# StreamDeck_CPU1-V0.net
KiCad netlist of a schematic drawn in Altium Designer
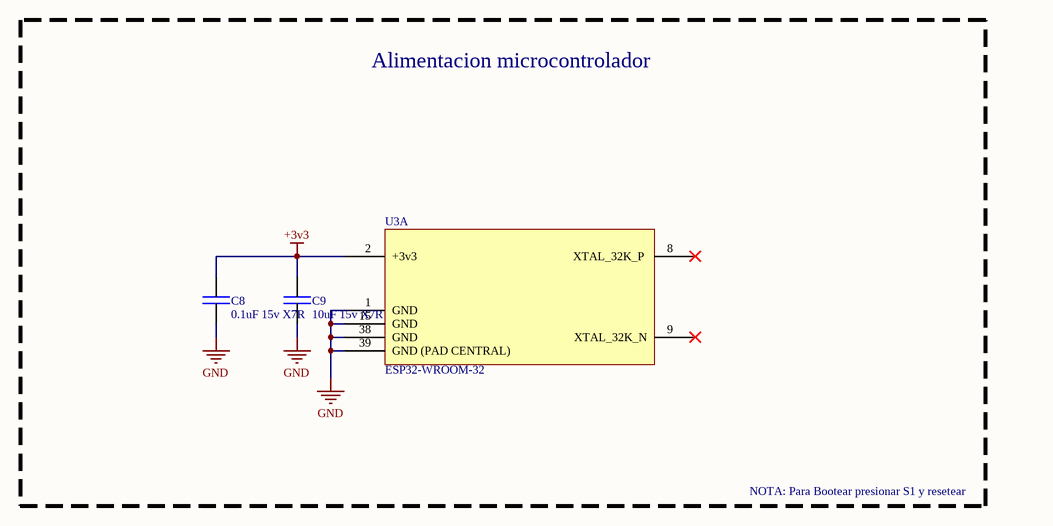
[diagram p0: StreamDeck_CPU1-V0.SchDoc]

(export (version "E")
  (design (tool "Eeschema 10.0.6"))
  (components
    (comp (ref "C8")
      (value "0.1uF 15v X7R")
      (footprint "C_0805")
      (description "Capacitor no polarizado")
      (libsource (lib "StreamDeck-V0") (part "Capacitor NP"))
    )
    (comp (ref "C9")
      (value "10uF 15v X7R")
      (footprint "C_0805")
      (description "Capacitor no polarizado")
      (libsource (lib "StreamDeck-V0") (part "Capacitor NP"))
    )
    (comp (ref "U3")
      (value "ESP32-WROOM-32")
      (footprint "Espressif ESP32-WROOM-32")
      (libsource (lib "StreamDeck-V0") (part "ESP32"))
    )
  )
  (nets
    (net (code "1") (name "+3v3") (class "Default")
      (node (ref "C8") (pin "1") (pinfunction "1_1") (pintype "passive"))
      (node (ref "C9") (pin "1") (pinfunction "1_1") (pintype "passive"))
      (node (ref "U3") (pin "2") (pinfunction "+3v3_2") (pintype "power_in"))
    )
    (net (code "2") (name "GND") (class "Default")
      (node (ref "C8") (pin "2") (pinfunction "2_2") (pintype "passive"))
      (node (ref "C9") (pin "2") (pinfunction "2_2") (pintype "passive"))
      (node (ref "U3") (pin "1") (pinfunction "GND_1") (pintype "power_in"))
      (node (ref "U3") (pin "15") (pinfunction "GND_15") (pintype "power_in"))
      (node (ref "U3") (pin "38") (pinfunction "GND_38") (pintype "power_in"))
      (node (ref "U3") (pin "39") (pinfunction "GND_(PAD_CENTRAL)_39") (pintype "power_in"))
    )
    (net (code "3") (name "unconnected-(U3A-XTAL_32K_N-Pad9)") (class "Default")
      (node (ref "U3") (pin "9") (pinfunction "XTAL_32K_N_9") (pintype "passive+no_connect"))
    )
    (net (code "4") (name "unconnected-(U3A-XTAL_32K_P-Pad8)") (class "Default")
      (node (ref "U3") (pin "8") (pinfunction "XTAL_32K_P_8") (pintype "passive+no_connect"))
    )
  )
)
